# peregigateli.net
KiCad netlist of a schematic drawn in EAGLE
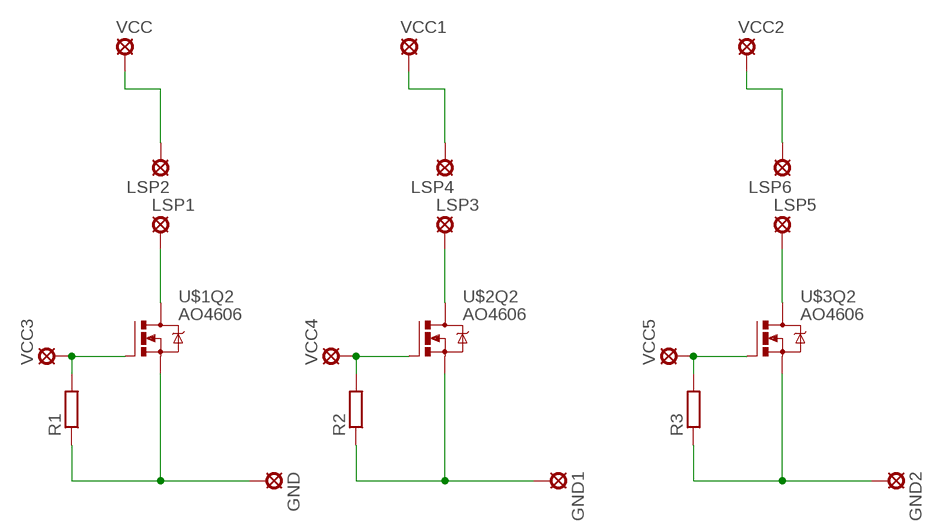
[diagram p0: schematic, sheet 1]

(export (version "E")
  (design (tool "Eeschema 10.0.6"))
  (components
    (comp (ref "GND")
      (value "LSP10")
      (footprint "eagle-import:LSP10")
      (libsource (lib "eagle-import") (part "LSP10"))
    )
    (comp (ref "GND1")
      (value "LSP10")
      (footprint "eagle-import:LSP10")
      (libsource (lib "eagle-import") (part "LSP10"))
    )
    (comp (ref "GND2")
      (value "LSP10")
      (footprint "eagle-import:LSP10")
      (libsource (lib "eagle-import") (part "LSP10"))
    )
    (comp (ref "LSP1")
      (value "LSP10")
      (footprint "eagle-import:LSP10")
      (libsource (lib "eagle-import") (part "LSP10"))
    )
    (comp (ref "LSP2")
      (value "LSP10")
      (footprint "eagle-import:LSP10")
      (libsource (lib "eagle-import") (part "LSP10"))
    )
    (comp (ref "LSP3")
      (value "LSP10")
      (footprint "eagle-import:LSP10")
      (libsource (lib "eagle-import") (part "LSP10"))
    )
    (comp (ref "LSP4")
      (value "LSP10")
      (footprint "eagle-import:LSP10")
      (libsource (lib "eagle-import") (part "LSP10"))
    )
    (comp (ref "LSP5")
      (value "LSP10")
      (footprint "eagle-import:LSP10")
      (libsource (lib "eagle-import") (part "LSP10"))
    )
    (comp (ref "LSP6")
      (value "LSP10")
      (footprint "eagle-import:LSP10")
      (libsource (lib "eagle-import") (part "LSP10"))
    )
    (comp (ref "R1")
      (value "R-EU_0207/10")
      (footprint "eagle-import:0207_10")
      (libsource (lib "eagle-import") (part "R-EU_0207/10"))
    )
    (comp (ref "R2")
      (value "R-EU_0207/10")
      (footprint "eagle-import:0207_10")
      (libsource (lib "eagle-import") (part "R-EU_0207/10"))
    )
    (comp (ref "R3")
      (value "R-EU_0207/10")
      (footprint "eagle-import:0207_10")
      (libsource (lib "eagle-import") (part "R-EU_0207/10"))
    )
    (comp (ref "U$1")
      (value "AO4606")
      (footprint "eagle-import:SOIC-8")
      (libsource (lib "eagle-import") (part "AO4606"))
    )
    (comp (ref "U$2")
      (value "AO4606")
      (footprint "eagle-import:SOIC-8")
      (libsource (lib "eagle-import") (part "AO4606"))
    )
    (comp (ref "U$3")
      (value "AO4606")
      (footprint "eagle-import:SOIC-8")
      (libsource (lib "eagle-import") (part "AO4606"))
    )
    (comp (ref "VCC")
      (value "LSP10")
      (footprint "eagle-import:LSP10")
      (libsource (lib "eagle-import") (part "LSP10"))
    )
    (comp (ref "VCC1")
      (value "LSP10")
      (footprint "eagle-import:LSP10")
      (libsource (lib "eagle-import") (part "LSP10"))
    )
    (comp (ref "VCC2")
      (value "LSP10")
      (footprint "eagle-import:LSP10")
      (libsource (lib "eagle-import") (part "LSP10"))
    )
    (comp (ref "VCC3")
      (value "LSP10")
      (footprint "eagle-import:LSP10")
      (libsource (lib "eagle-import") (part "LSP10"))
    )
    (comp (ref "VCC4")
      (value "LSP10")
      (footprint "eagle-import:LSP10")
      (libsource (lib "eagle-import") (part "LSP10"))
    )
    (comp (ref "VCC5")
      (value "LSP10")
      (footprint "eagle-import:LSP10")
      (libsource (lib "eagle-import") (part "LSP10"))
    )
  )
  (nets
    (net (code "1") (name "Net-(LSP1-PadMP)") (class "Default")
      (node (ref "LSP1") (pin "MP") (pinfunction "MP_MP") (pintype "passive"))
      (node (ref "U$1") (pin "7") (pinfunction "D_7") (pintype "passive"))
      (node (ref "U$1") (pin "8") (pinfunction "D_8") (pintype "passive"))
    )
    (net (code "2") (name "Net-(LSP2-PadMP)") (class "Default")
      (node (ref "LSP2") (pin "MP") (pinfunction "MP_MP") (pintype "passive"))
      (node (ref "VCC") (pin "MP") (pinfunction "MP_MP") (pintype "passive"))
    )
    (net (code "3") (name "Net-(LSP3-PadMP)") (class "Default")
      (node (ref "LSP3") (pin "MP") (pinfunction "MP_MP") (pintype "passive"))
      (node (ref "U$2") (pin "7") (pinfunction "D_7") (pintype "passive"))
      (node (ref "U$2") (pin "8") (pinfunction "D_8") (pintype "passive"))
    )
    (net (code "4") (name "Net-(LSP4-PadMP)") (class "Default")
      (node (ref "LSP4") (pin "MP") (pinfunction "MP_MP") (pintype "passive"))
      (node (ref "VCC1") (pin "MP") (pinfunction "MP_MP") (pintype "passive"))
    )
    (net (code "5") (name "Net-(LSP5-PadMP)") (class "Default")
      (node (ref "LSP5") (pin "MP") (pinfunction "MP_MP") (pintype "passive"))
      (node (ref "U$3") (pin "7") (pinfunction "D_7") (pintype "passive"))
      (node (ref "U$3") (pin "8") (pinfunction "D_8") (pintype "passive"))
    )
    (net (code "6") (name "Net-(LSP6-PadMP)") (class "Default")
      (node (ref "LSP6") (pin "MP") (pinfunction "MP_MP") (pintype "passive"))
      (node (ref "VCC2") (pin "MP") (pinfunction "MP_MP") (pintype "passive"))
    )
    (net (code "7") (name "Net-(U$1B-G)") (class "Default")
      (node (ref "R1") (pin "2") (pinfunction "2_2") (pintype "passive"))
      (node (ref "U$1") (pin "2") (pinfunction "G_2") (pintype "passive"))
      (node (ref "VCC3") (pin "MP") (pinfunction "MP_MP") (pintype "passive"))
    )
    (net (code "8") (name "Net-(U$1B-S)") (class "Default")
      (node (ref "GND") (pin "MP") (pinfunction "MP_MP") (pintype "passive"))
      (node (ref "R1") (pin "1") (pinfunction "1_1") (pintype "passive"))
      (node (ref "U$1") (pin "1") (pinfunction "S_1") (pintype "passive"))
    )
    (net (code "9") (name "Net-(U$2B-G)") (class "Default")
      (node (ref "R2") (pin "2") (pinfunction "2_2") (pintype "passive"))
      (node (ref "U$2") (pin "2") (pinfunction "G_2") (pintype "passive"))
      (node (ref "VCC4") (pin "MP") (pinfunction "MP_MP") (pintype "passive"))
    )
    (net (code "10") (name "Net-(U$2B-S)") (class "Default")
      (node (ref "GND1") (pin "MP") (pinfunction "MP_MP") (pintype "passive"))
      (node (ref "R2") (pin "1") (pinfunction "1_1") (pintype "passive"))
      (node (ref "U$2") (pin "1") (pinfunction "S_1") (pintype "passive"))
    )
    (net (code "11") (name "Net-(U$3B-G)") (class "Default")
      (node (ref "R3") (pin "2") (pinfunction "2_2") (pintype "passive"))
      (node (ref "U$3") (pin "2") (pinfunction "G_2") (pintype "passive"))
      (node (ref "VCC5") (pin "MP") (pinfunction "MP_MP") (pintype "passive"))
    )
    (net (code "12") (name "Net-(U$3B-S)") (class "Default")
      (node (ref "GND2") (pin "MP") (pinfunction "MP_MP") (pintype "passive"))
      (node (ref "R3") (pin "1") (pinfunction "1_1") (pintype "passive"))
      (node (ref "U$3") (pin "1") (pinfunction "S_1") (pintype "passive"))
    )
  )
)
